# sb-sonata-fpganaalog.net
KiCad netlist of a schematic drawn in Altium Designer
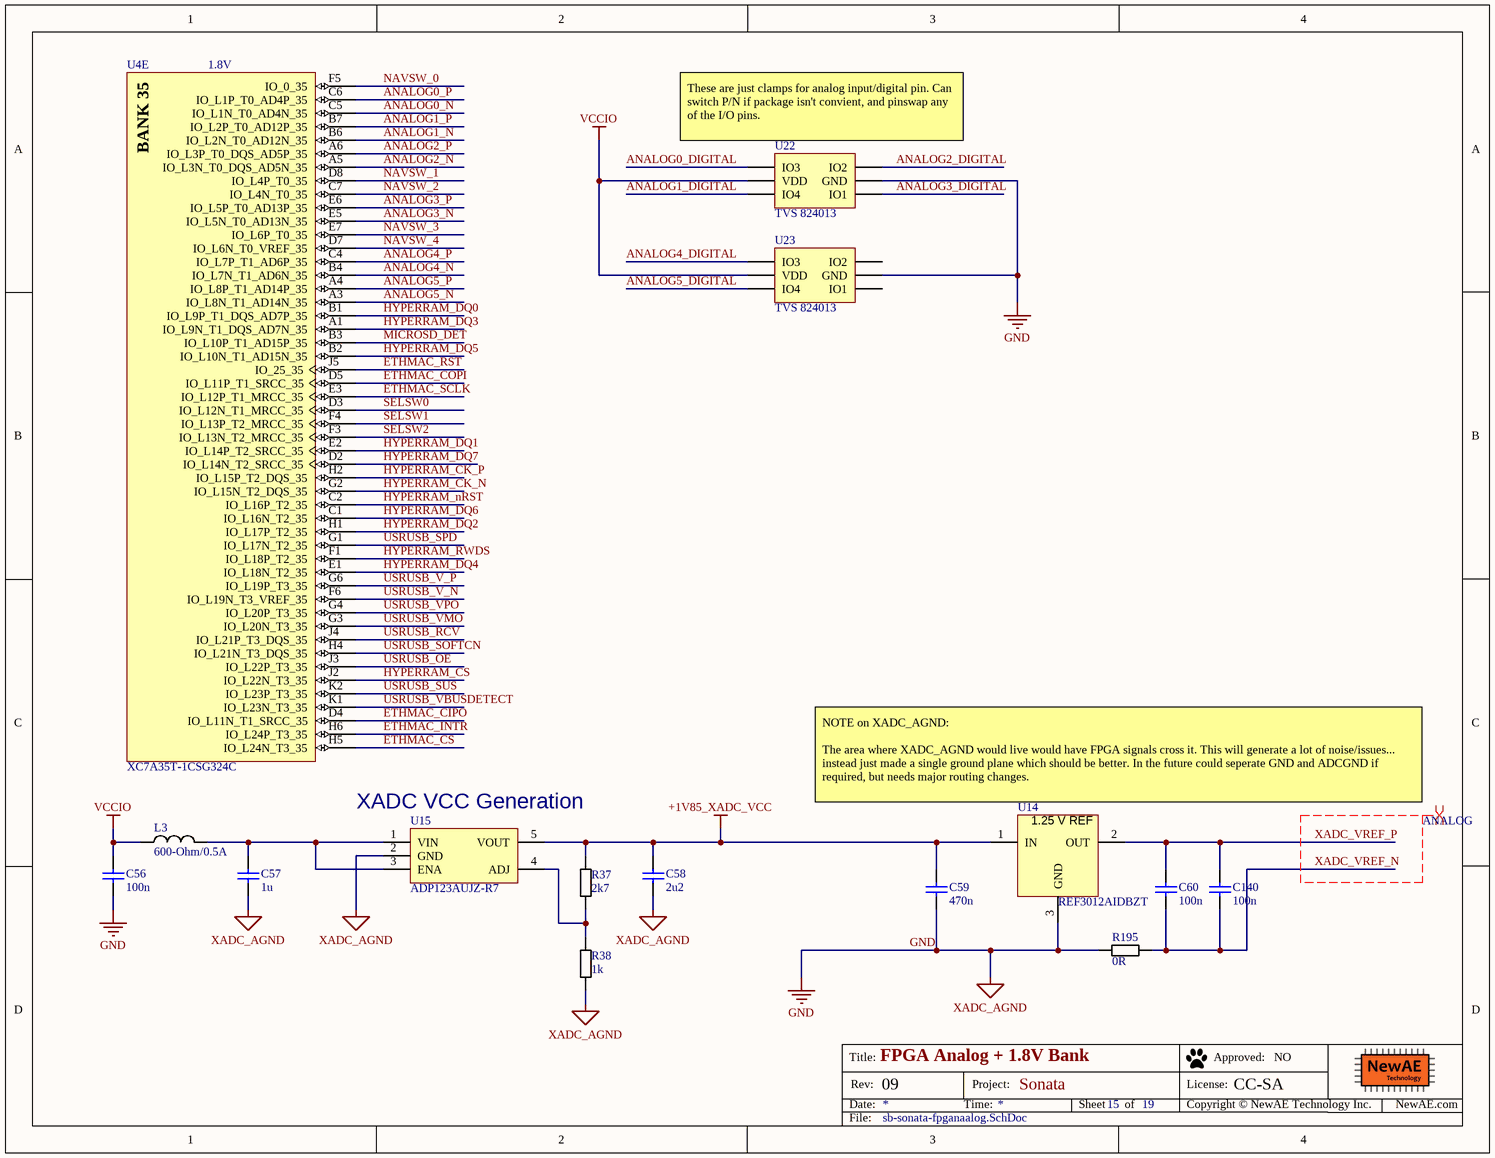
[diagram p0: sb-sonata-fpganaalog.SchDoc]

(export (version "E")
  (design (tool "Eeschema 10.0.6"))
  (components
    (comp (ref "C56")
      (value "100n")
      (footprint "CAPC0402_M")
      (description "100n, 0402")
      (fields (field (name "PART NUMBER") "CCHIP-100n-0402"))
      (libsource (lib "NewAE_AltiumLib") (part "CAP"))
    )
    (comp (ref "C57")
      (value "1u")
      (footprint "CAPC0603_M")
      (description "1u, 0603, 50V")
      (fields (field (name "PART NUMBER") "CCHIP-1u-0603"))
      (libsource (lib "NewAE_AltiumLib") (part "CAP"))
    )
    (comp (ref "C58")
      (value "2u2")
      (footprint "CAPC0603_M")
      (description "2u2, 0603")
      (fields (field (name "PART NUMBER") "CCHIP-2u2-0603-25V") (field (name "TOLERANCE") "±20%"))
      (libsource (lib "NewAE_AltiumLib") (part "CAP"))
    )
    (comp (ref "C59")
      (value "470n")
      (footprint "CAPC0603_M")
      (description "470n, 0603, 50V")
      (fields (field (name "PART NUMBER") "CCHIP-470n-0603-50V"))
      (libsource (lib "NewAE_AltiumLib") (part "CAP"))
    )
    (comp (ref "C60")
      (value "100n")
      (footprint "CAPC0402_M")
      (description "100n, 0402")
      (fields (field (name "PART NUMBER") "CCHIP-100n-0402"))
      (libsource (lib "NewAE_AltiumLib") (part "CAP"))
    )
    (comp (ref "C140")
      (value "100n")
      (footprint "CAPC0402_M")
      (description "100n, 0402")
      (fields (field (name "PART NUMBER") "CCHIP-100n-0402"))
      (libsource (lib "NewAE_AltiumLib") (part "CAP"))
    )
    (comp (ref "L3")
      (value "600-Ohm/0.5A")
      (footprint "IND_0603")
      (description "600 Ohm @ 100 MHz, 0.5A rated FB")
      (fields (field (name "PART NUMBER") "FBCHIP-600R-0603"))
      (libsource (lib "NewAE_AltiumLib") (part "IND"))
    )
    (comp (ref "R37")
      (value "2k7")
      (footprint "RESC1005X40N")
      (description "2k7 res, 0402, 1%, 1/16W")
      (fields (field (name "PART NUMBER") "RCHIP-2K7-0402") (field (name "TOLERANCE") "1%"))
      (libsource (lib "NewAE_AltiumLib") (part "RES-EU"))
    )
    (comp (ref "R38")
      (value "1k")
      (footprint "RESC1005X40N")
      (description "1k res, 0402, 1%, 1/16W")
      (fields (field (name "PART NUMBER") "RCHIP-1K-0402") (field (name "TOLERANCE") "1%"))
      (libsource (lib "NewAE_AltiumLib") (part "RES-EU"))
    )
    (comp (ref "R195")
      (value "0R")
      (footprint "RESC1005X40N")
      (description "2 ohm")
      (fields (field (name "PART NUMBER") "RCHIP-0R-0402"))
      (libsource (lib "") (part "RES-EU_1"))
    )
    (comp (ref "U4")
      (value "XC7A35T-1CSG324C")
      (footprint "CSG324")
      (description "Artix-7 FPGA, 210 User I/Os, 0 GTP, 324-Ball BGA, Speed Grade 1, Commercial Grade, Pb-Free")
      (fields (field (name "MANUFACTURER") "Xilinx"))
      (libsource (lib "Altium Content Vault") (part "XLNX-XC7A35T-CSG324"))
    )
    (comp (ref "U14")
      (value "REF3012AIDBZT")
      (footprint "SOT95P237X112-3N")
      (description "IC VREF SERIES 0.2% SOT23-3")
      (fields (field (name "MANUFACTURER PART NUMBER") "REF3012AIDBZT"))
      (libsource (lib "NewAE_AltiumLib") (part "REF3012AIDBZT"))
    )
    (comp (ref "U15")
      (value "Linear Voltage Regulator IC  1 Output  300mA TSOT-5")
      (footprint "SOT23-5P95_285X145L45X40")
      (description "IC REG LIN POS ADJ 300MA TSOT5")
      (fields
        (field (name "MANUFACTURER PART NUMBER") "ADP123AUJZ-R7")
        (field (name "PART NUMBER") "ADP123AUJZ-R7")
      )
      (libsource (lib "NewAE_AltiumLib") (part "ADP123AUJZ-R7"))
    )
    (comp (ref "U22")
      (value "TVS 824013")
      (footprint "SOT95P280X145-6N")
      (description "TVS DIODE 3.3V 6V SOT23-6L")
      (fields (field (name "PART NUMBER") "TVS_4IO_3v3"))
      (libsource (lib "NewAE_AltiumLib") (part "IO_Clamp_x4_3v3_824013"))
    )
    (comp (ref "U23")
      (value "TVS 824013")
      (footprint "SOT95P280X145-6N")
      (description "TVS DIODE 3.3V 6V SOT23-6L")
      (fields (field (name "PART NUMBER") "TVS_4IO_3v3"))
      (libsource (lib "NewAE_AltiumLib") (part "IO_Clamp_x4_3v3_824013"))
    )
  )
  (nets
    (net (code "1") (name "+1V85_XADC_VCC") (class "Default")
      (node (ref "C58") (pin "1") (pinfunction "1_1") (pintype "passive"))
      (node (ref "C59") (pin "1") (pinfunction "1_1") (pintype "passive"))
      (node (ref "R37") (pin "1") (pinfunction "1_1") (pintype "passive"))
      (node (ref "U14") (pin "1") (pinfunction "IN_1") (pintype "passive"))
      (node (ref "U15") (pin "5") (pinfunction "VOUT_5") (pintype "passive"))
    )
    (net (code "2") (name "/ANALOG0_DIGITAL") (class "Default")
      (node (ref "U22") (pin "4") (pinfunction "IO3_4") (pintype "passive"))
    )
    (net (code "3") (name "/ANALOG0_N") (class "Default")
      (node (ref "U4") (pin "C5") (pinfunction "IO_L1N_T0_AD4N_35_C5") (pintype "bidirectional"))
    )
    (net (code "4") (name "/ANALOG0_P") (class "Default")
      (node (ref "U4") (pin "C6") (pinfunction "IO_L1P_T0_AD4P_35_C6") (pintype "bidirectional"))
    )
    (net (code "5") (name "/ANALOG1_DIGITAL") (class "Default")
      (node (ref "U22") (pin "6") (pinfunction "IO4_6") (pintype "passive"))
    )
    (net (code "6") (name "/ANALOG1_N") (class "Default")
      (node (ref "U4") (pin "B6") (pinfunction "IO_L2N_T0_AD12N_35_B6") (pintype "bidirectional"))
    )
    (net (code "7") (name "/ANALOG1_P") (class "Default")
      (node (ref "U4") (pin "B7") (pinfunction "IO_L2P_T0_AD12P_35_B7") (pintype "bidirectional"))
    )
    (net (code "8") (name "/ANALOG2_DIGITAL") (class "Default")
      (node (ref "U22") (pin "3") (pinfunction "IO2_3") (pintype "passive"))
    )
    (net (code "9") (name "/ANALOG2_N") (class "Default")
      (node (ref "U4") (pin "A5") (pinfunction "IO_L3N_T0_DQS_AD5N_35_A5") (pintype "bidirectional"))
    )
    (net (code "10") (name "/ANALOG2_P") (class "Default")
      (node (ref "U4") (pin "A6") (pinfunction "IO_L3P_T0_DQS_AD5P_35_A6") (pintype "bidirectional"))
    )
    (net (code "11") (name "/ANALOG3_DIGITAL") (class "Default")
      (node (ref "U22") (pin "1") (pinfunction "IO1_1") (pintype "passive"))
    )
    (net (code "12") (name "/ANALOG3_N") (class "Default")
      (node (ref "U4") (pin "E5") (pinfunction "IO_L5N_T0_AD13N_35_E5") (pintype "bidirectional"))
    )
    (net (code "13") (name "/ANALOG3_P") (class "Default")
      (node (ref "U4") (pin "E6") (pinfunction "IO_L5P_T0_AD13P_35_E6") (pintype "bidirectional"))
    )
    (net (code "14") (name "/ANALOG4_DIGITAL") (class "Default")
      (node (ref "U23") (pin "4") (pinfunction "IO3_4") (pintype "passive"))
    )
    (net (code "15") (name "/ANALOG4_N") (class "Default")
      (node (ref "U4") (pin "B4") (pinfunction "IO_L7N_T1_AD6N_35_B4") (pintype "bidirectional"))
    )
    (net (code "16") (name "/ANALOG4_P") (class "Default")
      (node (ref "U4") (pin "C4") (pinfunction "IO_L7P_T1_AD6P_35_C4") (pintype "bidirectional"))
    )
    (net (code "17") (name "/ANALOG5_DIGITAL") (class "Default")
      (node (ref "U23") (pin "6") (pinfunction "IO4_6") (pintype "passive"))
    )
    (net (code "18") (name "/ANALOG5_N") (class "Default")
      (node (ref "U4") (pin "A3") (pinfunction "IO_L8N_T1_AD14N_35_A3") (pintype "bidirectional"))
    )
    (net (code "19") (name "/ANALOG5_P") (class "Default")
      (node (ref "U4") (pin "A4") (pinfunction "IO_L8P_T1_AD14P_35_A4") (pintype "bidirectional"))
    )
    (net (code "20") (name "/ETHMAC_CIPO") (class "Default")
      (node (ref "U4") (pin "D4") (pinfunction "IO_L11N_T1_SRCC_35_D4") (pintype "bidirectional"))
    )
    (net (code "21") (name "/ETHMAC_COPI") (class "Default")
      (node (ref "U4") (pin "D5") (pinfunction "IO_L11P_T1_SRCC_35_D5") (pintype "bidirectional"))
    )
    (net (code "22") (name "/ETHMAC_CS") (class "Default")
      (node (ref "U4") (pin "H5") (pinfunction "IO_L24N_T3_35_H5") (pintype "bidirectional"))
    )
    (net (code "23") (name "/ETHMAC_INTR") (class "Default")
      (node (ref "U4") (pin "H6") (pinfunction "IO_L24P_T3_35_H6") (pintype "bidirectional"))
    )
    (net (code "24") (name "/ETHMAC_RST") (class "Default")
      (node (ref "U4") (pin "J5") (pinfunction "IO_25_35_J5") (pintype "bidirectional"))
    )
    (net (code "25") (name "/ETHMAC_SCLK") (class "Default")
      (node (ref "U4") (pin "E3") (pinfunction "IO_L12P_T1_MRCC_35_E3") (pintype "bidirectional"))
    )
    (net (code "26") (name "/HYPERRAM_CK_N") (class "Default")
      (node (ref "U4") (pin "G2") (pinfunction "IO_L15N_T2_DQS_35_G2") (pintype "bidirectional"))
    )
    (net (code "27") (name "/HYPERRAM_CK_P") (class "Default")
      (node (ref "U4") (pin "H2") (pinfunction "IO_L15P_T2_DQS_35_H2") (pintype "bidirectional"))
    )
    (net (code "28") (name "/HYPERRAM_CS") (class "Default")
      (node (ref "U4") (pin "J2") (pinfunction "IO_L22N_T3_35_J2") (pintype "bidirectional"))
    )
    (net (code "29") (name "/HYPERRAM_DQ0") (class "Default")
      (node (ref "U4") (pin "B1") (pinfunction "IO_L9P_T1_DQS_AD7P_35_B1") (pintype "bidirectional"))
    )
    (net (code "30") (name "/HYPERRAM_DQ1") (class "Default")
      (node (ref "U4") (pin "E2") (pinfunction "IO_L14P_T2_SRCC_35_E2") (pintype "bidirectional"))
    )
    (net (code "31") (name "/HYPERRAM_DQ2") (class "Default")
      (node (ref "U4") (pin "H1") (pinfunction "IO_L17P_T2_35_H1") (pintype "bidirectional"))
    )
    (net (code "32") (name "/HYPERRAM_DQ3") (class "Default")
      (node (ref "U4") (pin "A1") (pinfunction "IO_L9N_T1_DQS_AD7N_35_A1") (pintype "bidirectional"))
    )
    (net (code "33") (name "/HYPERRAM_DQ4") (class "Default")
      (node (ref "U4") (pin "E1") (pinfunction "IO_L18N_T2_35_E1") (pintype "bidirectional"))
    )
    (net (code "34") (name "/HYPERRAM_DQ5") (class "Default")
      (node (ref "U4") (pin "B2") (pinfunction "IO_L10N_T1_AD15N_35_B2") (pintype "bidirectional"))
    )
    (net (code "35") (name "/HYPERRAM_DQ6") (class "Default")
      (node (ref "U4") (pin "C1") (pinfunction "IO_L16N_T2_35_C1") (pintype "bidirectional"))
    )
    (net (code "36") (name "/HYPERRAM_DQ7") (class "Default")
      (node (ref "U4") (pin "D2") (pinfunction "IO_L14N_T2_SRCC_35_D2") (pintype "bidirectional"))
    )
    (net (code "37") (name "/HYPERRAM_RWDS") (class "Default")
      (node (ref "U4") (pin "F1") (pinfunction "IO_L18P_T2_35_F1") (pintype "bidirectional"))
    )
    (net (code "38") (name "/HYPERRAM_nRST") (class "Default")
      (node (ref "U4") (pin "C2") (pinfunction "IO_L16P_T2_35_C2") (pintype "bidirectional"))
    )
    (net (code "39") (name "/MICROSD_DET") (class "Default")
      (node (ref "U4") (pin "B3") (pinfunction "IO_L10P_T1_AD15P_35_B3") (pintype "bidirectional"))
    )
    (net (code "40") (name "/NAVSW_0") (class "Default")
      (node (ref "U4") (pin "F5") (pinfunction "IO_0_35_F5") (pintype "bidirectional"))
    )
    (net (code "41") (name "/NAVSW_1") (class "Default")
      (node (ref "U4") (pin "D8") (pinfunction "IO_L4P_T0_35_D8") (pintype "bidirectional"))
    )
    (net (code "42") (name "/NAVSW_2") (class "Default")
      (node (ref "U4") (pin "C7") (pinfunction "IO_L4N_T0_35_C7") (pintype "bidirectional"))
    )
    (net (code "43") (name "/NAVSW_3") (class "Default")
      (node (ref "U4") (pin "E7") (pinfunction "IO_L6P_T0_35_E7") (pintype "bidirectional"))
    )
    (net (code "44") (name "/NAVSW_4") (class "Default")
      (node (ref "U4") (pin "D7") (pinfunction "IO_L6N_T0_VREF_35_D7") (pintype "bidirectional"))
    )
    (net (code "45") (name "/SELSW0") (class "Default")
      (node (ref "U4") (pin "D3") (pinfunction "IO_L12N_T1_MRCC_35_D3") (pintype "bidirectional"))
    )
    (net (code "46") (name "/SELSW1") (class "Default")
      (node (ref "U4") (pin "F4") (pinfunction "IO_L13P_T2_MRCC_35_F4") (pintype "bidirectional"))
    )
    (net (code "47") (name "/SELSW2") (class "Default")
      (node (ref "U4") (pin "F3") (pinfunction "IO_L13N_T2_MRCC_35_F3") (pintype "bidirectional"))
    )
    (net (code "48") (name "/USRUSB_OE") (class "Default")
      (node (ref "U4") (pin "J3") (pinfunction "IO_L22P_T3_35_J3") (pintype "bidirectional"))
    )
    (net (code "49") (name "/USRUSB_RCV") (class "Default")
      (node (ref "U4") (pin "J4") (pinfunction "IO_L21P_T3_DQS_35_J4") (pintype "bidirectional"))
    )
    (net (code "50") (name "/USRUSB_SOFTCN") (class "Default")
      (node (ref "U4") (pin "H4") (pinfunction "IO_L21N_T3_DQS_35_H4") (pintype "bidirectional"))
    )
    (net (code "51") (name "/USRUSB_SPD") (class "Default")
      (node (ref "U4") (pin "G1") (pinfunction "IO_L17N_T2_35_G1") (pintype "bidirectional"))
    )
    (net (code "52") (name "/USRUSB_SUS") (class "Default")
      (node (ref "U4") (pin "K2") (pinfunction "IO_L23P_T3_35_K2") (pintype "bidirectional"))
    )
    (net (code "53") (name "/USRUSB_VBUSDETECT") (class "Default")
      (node (ref "U4") (pin "K1") (pinfunction "IO_L23N_T3_35_K1") (pintype "bidirectional"))
    )
    (net (code "54") (name "/USRUSB_VMO") (class "Default")
      (node (ref "U4") (pin "G3") (pinfunction "IO_L20N_T3_35_G3") (pintype "bidirectional"))
    )
    (net (code "55") (name "/USRUSB_VPO") (class "Default")
      (node (ref "U4") (pin "G4") (pinfunction "IO_L20P_T3_35_G4") (pintype "bidirectional"))
    )
    (net (code "56") (name "/USRUSB_V_N") (class "Default")
      (node (ref "U4") (pin "F6") (pinfunction "IO_L19N_T3_VREF_35_F6") (pintype "bidirectional"))
    )
    (net (code "57") (name "/USRUSB_V_P") (class "Default")
      (node (ref "U4") (pin "G6") (pinfunction "IO_L19P_T3_35_G6") (pintype "bidirectional"))
    )
    (net (code "58") (name "/XADC_VREF_N") (class "Default")
      (node (ref "C140") (pin "2") (pinfunction "2_2") (pintype "passive"))
      (node (ref "C60") (pin "2") (pinfunction "2_2") (pintype "passive"))
      (node (ref "R195") (pin "2") (pinfunction "2_2") (pintype "passive"))
    )
    (net (code "59") (name "/XADC_VREF_P") (class "Default")
      (node (ref "C140") (pin "1") (pinfunction "1_1") (pintype "passive"))
      (node (ref "C60") (pin "1") (pinfunction "1_1") (pintype "passive"))
      (node (ref "U14") (pin "2") (pinfunction "OUT_2") (pintype "passive"))
    )
    (net (code "60") (name "GND") (class "Default")
      (node (ref "C56") (pin "2") (pinfunction "2_2") (pintype "passive"))
      (node (ref "C57") (pin "2") (pinfunction "2_2") (pintype "passive"))
      (node (ref "C58") (pin "2") (pinfunction "2_2") (pintype "passive"))
      (node (ref "C59") (pin "2") (pinfunction "2_2") (pintype "passive"))
      (node (ref "R195") (pin "1") (pinfunction "1_1") (pintype "passive"))
      (node (ref "R38") (pin "2") (pinfunction "2_2") (pintype "passive"))
      (node (ref "U14") (pin "3") (pinfunction "GND_3") (pintype "passive"))
      (node (ref "U15") (pin "2") (pinfunction "GND_2") (pintype "passive"))
      (node (ref "U22") (pin "2") (pinfunction "GND_2") (pintype "passive"))
      (node (ref "U23") (pin "2") (pinfunction "GND_2") (pintype "passive"))
    )
    (net (code "61") (name "Net-(U15-ADJ)") (class "Default")
      (node (ref "R37") (pin "2") (pinfunction "2_2") (pintype "passive"))
      (node (ref "R38") (pin "1") (pinfunction "1_1") (pintype "passive"))
      (node (ref "U15") (pin "4") (pinfunction "ADJ_4") (pintype "passive"))
    )
    (net (code "62") (name "Net-(U15-ENA)") (class "Default")
      (node (ref "C57") (pin "1") (pinfunction "1_1") (pintype "passive"))
      (node (ref "L3") (pin "2") (pinfunction "2_2") (pintype "passive"))
      (node (ref "U15") (pin "1") (pinfunction "VIN_1") (pintype "passive"))
      (node (ref "U15") (pin "3") (pinfunction "ENA_3") (pintype "passive"))
    )
    (net (code "63") (name "VCCIO") (class "Default")
      (node (ref "C56") (pin "1") (pinfunction "1_1") (pintype "passive"))
      (node (ref "L3") (pin "1") (pinfunction "1_1") (pintype "passive"))
      (node (ref "U22") (pin "5") (pinfunction "VDD_5") (pintype "passive"))
      (node (ref "U23") (pin "5") (pinfunction "VDD_5") (pintype "passive"))
    )
    (net (code "64") (name "unconnected-(U23-IO1-Pad1)") (class "Default")
      (node (ref "U23") (pin "1") (pinfunction "IO1_1") (pintype "passive"))
    )
    (net (code "65") (name "unconnected-(U23-IO2-Pad3)") (class "Default")
      (node (ref "U23") (pin "3") (pinfunction "IO2_3") (pintype "passive"))
    )
  )
)
